# main.net
KiCad netlist of a schematic drawn in EAGLE
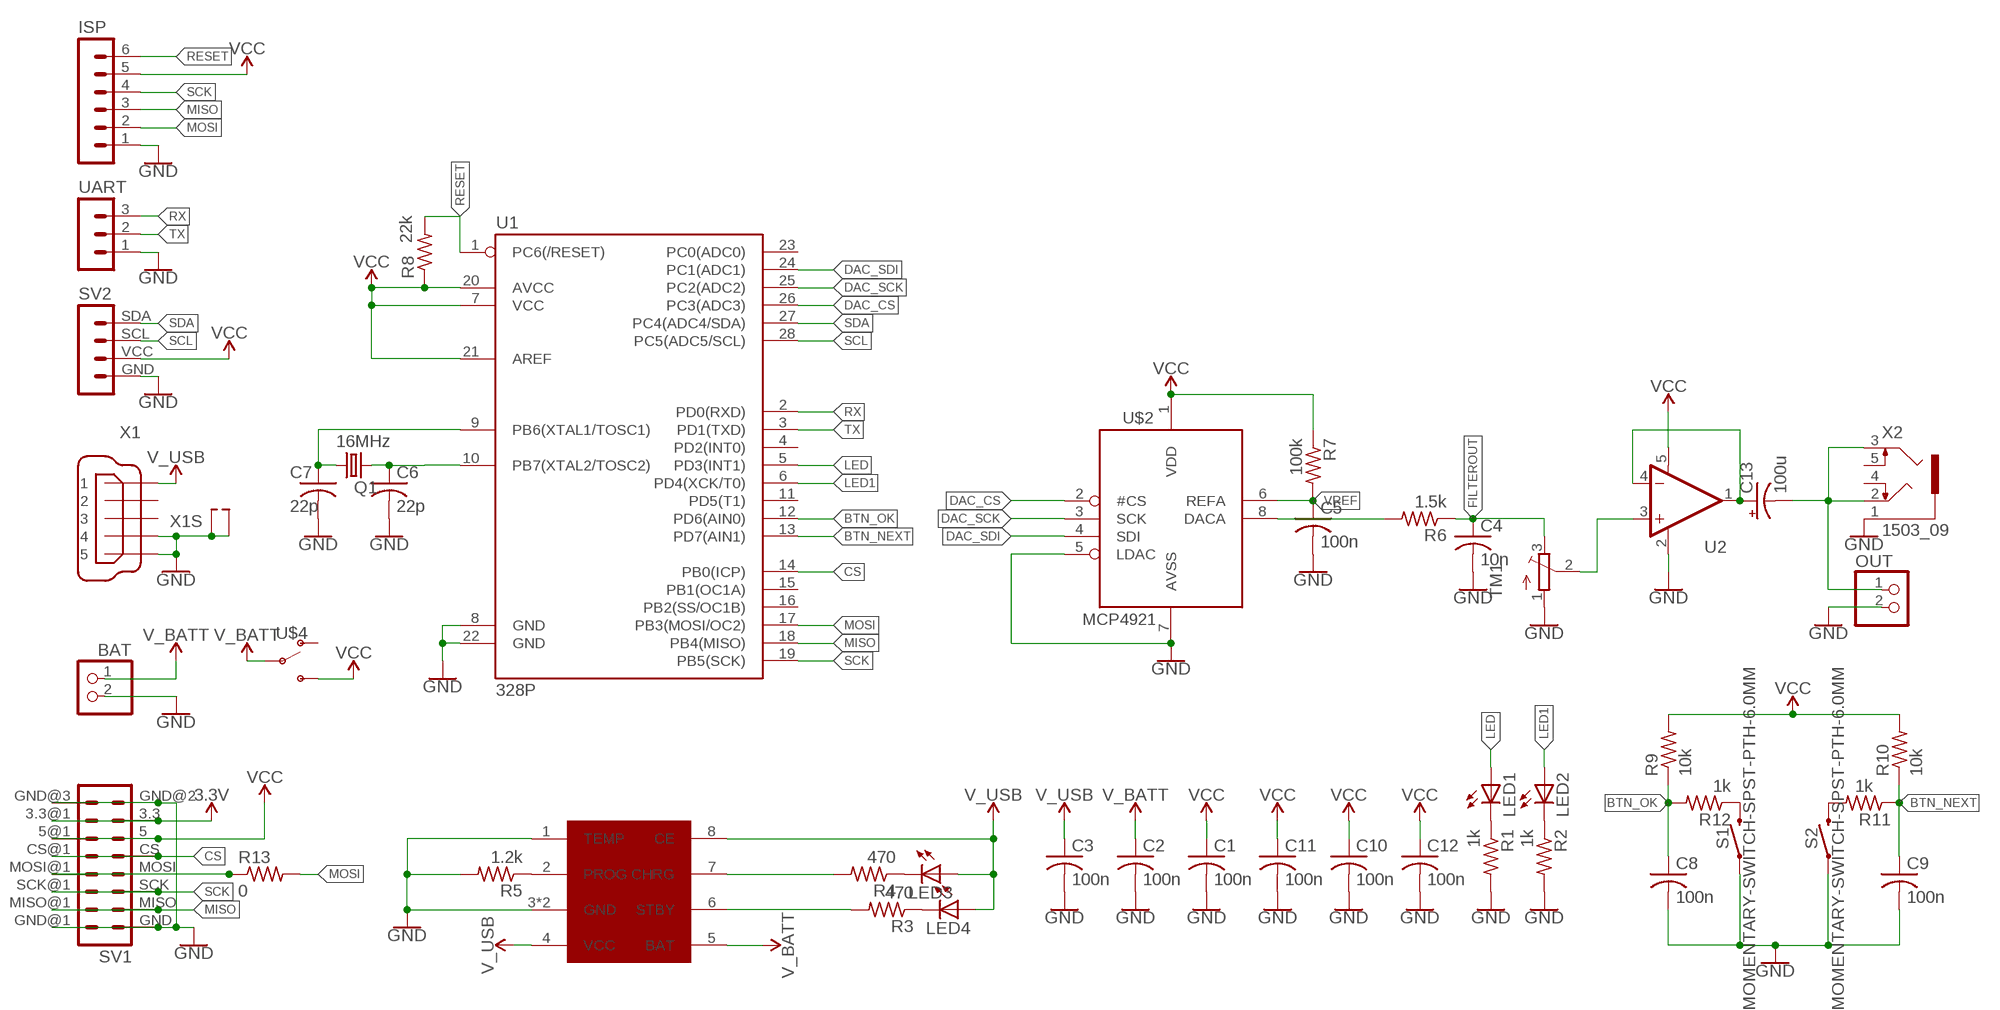
[diagram p0: schematic, sheet 1]

(export (version "E")
  (design (tool "Eeschema 10.0.6"))
  (components
    (comp (ref "BAT")
      (value "PINHD-1X2")
      (footprint "eagle-import:1X02")
      (libsource (lib "eagle-import") (part "PINHD-1X2"))
    )
    (comp (ref "C1")
      (value "100n")
      (footprint "eagle-import:C0603")
      (libsource (lib "eagle-import") (part "C-USC0603"))
    )
    (comp (ref "C2")
      (value "100n")
      (footprint "eagle-import:C0603")
      (libsource (lib "eagle-import") (part "C-USC0603"))
    )
    (comp (ref "C3")
      (value "100n")
      (footprint "eagle-import:C0603")
      (libsource (lib "eagle-import") (part "C-USC0603"))
    )
    (comp (ref "C4")
      (value "10n")
      (footprint "eagle-import:C0603")
      (libsource (lib "eagle-import") (part "C-USC0603"))
    )
    (comp (ref "C5")
      (value "100n")
      (footprint "eagle-import:C0603")
      (libsource (lib "eagle-import") (part "C-USC0603"))
    )
    (comp (ref "C6")
      (value "22p")
      (footprint "eagle-import:C0603")
      (libsource (lib "eagle-import") (part "C-USC0603"))
    )
    (comp (ref "C7")
      (value "22p")
      (footprint "eagle-import:C0603")
      (libsource (lib "eagle-import") (part "C-USC0603"))
    )
    (comp (ref "C8")
      (value "100n")
      (footprint "eagle-import:C0603")
      (libsource (lib "eagle-import") (part "C-USC0603"))
    )
    (comp (ref "C9")
      (value "100n")
      (footprint "eagle-import:C0603")
      (libsource (lib "eagle-import") (part "C-USC0603"))
    )
    (comp (ref "C10")
      (value "100n")
      (footprint "eagle-import:C0603")
      (libsource (lib "eagle-import") (part "C-USC0603"))
    )
    (comp (ref "C11")
      (value "100n")
      (footprint "eagle-import:C0603")
      (libsource (lib "eagle-import") (part "C-USC0603"))
    )
    (comp (ref "C12")
      (value "100n")
      (footprint "eagle-import:C0603")
      (libsource (lib "eagle-import") (part "C-USC0603"))
    )
    (comp (ref "C13")
      (value "100u")
      (footprint "eagle-import:E2,5-6E")
      (libsource (lib "eagle-import") (part "CPOL-USE2,5-6E"))
    )
    (comp (ref "CH1")
      (value "TP4056")
      (footprint "eagle-import:SOP8")
      (libsource (lib "eagle-import") (part "TP4056"))
    )
    (comp (ref "ISP")
      (value "MA06-1")
      (footprint "eagle-import:MA06-1")
      (libsource (lib "eagle-import") (part "MA06-1"))
    )
    (comp (ref "LED1")
      (value "LED3MM")
      (footprint "eagle-import:LED3MM")
      (libsource (lib "eagle-import") (part "LED3MM"))
    )
    (comp (ref "LED2")
      (value "LED3MM")
      (footprint "eagle-import:LED3MM")
      (libsource (lib "eagle-import") (part "LED3MM"))
    )
    (comp (ref "LED3")
      (value "LED3MM")
      (footprint "eagle-import:LED3MM")
      (libsource (lib "eagle-import") (part "LED3MM"))
    )
    (comp (ref "LED4")
      (value "LED3MM")
      (footprint "eagle-import:LED3MM")
      (libsource (lib "eagle-import") (part "LED3MM"))
    )
    (comp (ref "OUT")
      (value "PINHD-1X2")
      (footprint "eagle-import:1X02")
      (libsource (lib "eagle-import") (part "PINHD-1X2"))
    )
    (comp (ref "Q1")
      (value "16MHz")
      (footprint "eagle-import:HC49_S")
      (libsource (lib "eagle-import") (part "CRYSTALHC49S"))
    )
    (comp (ref "R1")
      (value "1k")
      (footprint "eagle-import:R0603")
      (libsource (lib "eagle-import") (part "R-US_R0603"))
    )
    (comp (ref "R2")
      (value "1k")
      (footprint "eagle-import:R0603")
      (libsource (lib "eagle-import") (part "R-US_R0603"))
    )
    (comp (ref "R3")
      (value "470")
      (footprint "eagle-import:R0603")
      (libsource (lib "eagle-import") (part "R-US_R0603"))
    )
    (comp (ref "R4")
      (value "470")
      (footprint "eagle-import:R0603")
      (libsource (lib "eagle-import") (part "R-US_R0603"))
    )
    (comp (ref "R5")
      (value "1.2k")
      (footprint "eagle-import:R0603")
      (libsource (lib "eagle-import") (part "R-US_R0603"))
    )
    (comp (ref "R6")
      (value "1.5k")
      (footprint "eagle-import:R0603")
      (libsource (lib "eagle-import") (part "R-US_R0603"))
    )
    (comp (ref "R7")
      (value "100k")
      (footprint "eagle-import:R0603")
      (libsource (lib "eagle-import") (part "R-US_R0603"))
    )
    (comp (ref "R8")
      (value "22k")
      (footprint "eagle-import:R0603")
      (libsource (lib "eagle-import") (part "R-US_R0603"))
    )
    (comp (ref "R9")
      (value "10k")
      (footprint "eagle-import:R0603")
      (libsource (lib "eagle-import") (part "R-US_R0603"))
    )
    (comp (ref "R10")
      (value "10k")
      (footprint "eagle-import:R0603")
      (libsource (lib "eagle-import") (part "R-US_R0603"))
    )
    (comp (ref "R11")
      (value "1k")
      (footprint "eagle-import:R0603")
      (libsource (lib "eagle-import") (part "R-US_R0603"))
    )
    (comp (ref "R12")
      (value "1k")
      (footprint "eagle-import:R0603")
      (libsource (lib "eagle-import") (part "R-US_R0603"))
    )
    (comp (ref "R13")
      (value "0")
      (footprint "eagle-import:0204_5")
      (libsource (lib "eagle-import") (part "R-US_0204/5"))
    )
    (comp (ref "S1")
      (value "MOMENTARY-SWITCH-SPST-PTH-6.0MM")
      (footprint "eagle-import:TACTILE_SWITCH_PTH_6.0MM")
      (libsource (lib "eagle-import") (part "MOMENTARY-SWITCH-SPST-PTH-6.0MM"))
    )
    (comp (ref "S2")
      (value "MOMENTARY-SWITCH-SPST-PTH-6.0MM")
      (footprint "eagle-import:TACTILE_SWITCH_PTH_6.0MM")
      (libsource (lib "eagle-import") (part "MOMENTARY-SWITCH-SPST-PTH-6.0MM"))
    )
    (comp (ref "SV1")
      (value "SD_CARD")
      (footprint "eagle-import:SD_CARD")
      (libsource (lib "eagle-import") (part "SD_CARD"))
    )
    (comp (ref "SV2")
      (value "OLED")
      (footprint "eagle-import:OLED")
      (libsource (lib "eagle-import") (part "OLED"))
    )
    (comp (ref "TM1")
      (value "TRIMPOT3386")
      (footprint "eagle-import:TRIM-3386")
      (libsource (lib "eagle-import") (part "TRIMPOT3386"))
    )
    (comp (ref "U$2")
      (value "MCP4921")
      (footprint "eagle-import:DIL08")
      (libsource (lib "eagle-import") (part "MCP4921"))
    )
    (comp (ref "U$4")
      (value "PC_SPDT_SWITCH")
      (footprint "eagle-import:PC_SPDT_SWITCH")
      (libsource (lib "eagle-import") (part "PC_SPDT_SWITCH"))
    )
    (comp (ref "U1")
      (value "328P")
      (footprint "eagle-import:DIP28")
      (libsource (lib "eagle-import") (part "ATMEGA328P_PDIP"))
    )
    (comp (ref "U2")
      (value "MCP6291T")
      (footprint "eagle-import:SOT23-5")
      (libsource (lib "eagle-import") (part "LMC7101T-E/OT"))
    )
    (comp (ref "UART")
      (value "MA03-1")
      (footprint "eagle-import:MA03-1")
      (libsource (lib "eagle-import") (part "MA03-1"))
    )
    (comp (ref "X1")
      (value "MINI-USB_SHIELD5P2-32005-601")
      (footprint "eagle-import:32005-601")
      (libsource (lib "eagle-import") (part "MINI-USB_SHIELD5P2-32005-601"))
    )
    (comp (ref "X2")
      (value "1503_09")
      (footprint "eagle-import:1503_09")
      (libsource (lib "eagle-import") (part "1503_09"))
    )
  )
  (nets
    (net (code "1") (name "3.3V") (class "Default")
      (node (ref "SV1") (pin "3.3") (pinfunction "3.3_3.3") (pintype "passive"))
      (node (ref "SV1") (pin "3.3@1") (pinfunction "3.3_3.3@1") (pintype "passive"))
    )
    (net (code "2") (name "BTN_NEXT") (class "Default")
      (node (ref "C9") (pin "1") (pinfunction "1_1") (pintype "passive"))
      (node (ref "R10") (pin "1") (pinfunction "1_1") (pintype "passive"))
      (node (ref "R11") (pin "1") (pinfunction "1_1") (pintype "passive"))
      (node (ref "U1") (pin "13") (pinfunction "PD7(AIN1)_13") (pintype "bidirectional"))
    )
    (net (code "3") (name "BTN_OK") (class "Default")
      (node (ref "C8") (pin "1") (pinfunction "1_1") (pintype "passive"))
      (node (ref "R12") (pin "2") (pinfunction "2_2") (pintype "passive"))
      (node (ref "R9") (pin "1") (pinfunction "1_1") (pintype "passive"))
      (node (ref "U1") (pin "12") (pinfunction "PD6(AIN0)_12") (pintype "bidirectional"))
    )
    (net (code "4") (name "CS") (class "Default")
      (node (ref "SV1") (pin "CS") (pinfunction "CS_CS") (pintype "passive"))
      (node (ref "SV1") (pin "CS@1") (pinfunction "CS_CS@1") (pintype "passive"))
      (node (ref "U1") (pin "14") (pinfunction "PB0(ICP)_14") (pintype "bidirectional"))
    )
    (net (code "5") (name "DAC_CS") (class "Default")
      (node (ref "U$2") (pin "2") (pinfunction "#CS_2") (pintype "input"))
      (node (ref "U1") (pin "26") (pinfunction "PC3(ADC3)_26") (pintype "bidirectional"))
    )
    (net (code "6") (name "DAC_SCK") (class "Default")
      (node (ref "U$2") (pin "3") (pinfunction "SCK_3") (pintype "input"))
      (node (ref "U1") (pin "25") (pinfunction "PC2(ADC2)_25") (pintype "bidirectional"))
    )
    (net (code "7") (name "DAC_SDI") (class "Default")
      (node (ref "U$2") (pin "4") (pinfunction "SDI_4") (pintype "input"))
      (node (ref "U1") (pin "24") (pinfunction "PC1(ADC1)_24") (pintype "bidirectional"))
    )
    (net (code "8") (name "FILTEROUT") (class "Default")
      (node (ref "C4") (pin "1") (pinfunction "1_1") (pintype "passive"))
      (node (ref "R6") (pin "1") (pinfunction "1_1") (pintype "passive"))
      (node (ref "TM1") (pin "3") (pinfunction "E_3") (pintype "passive"))
    )
    (net (code "9") (name "GND") (class "Default")
      (node (ref "BAT") (pin "2") (pinfunction "2_2") (pintype "passive"))
      (node (ref "C1") (pin "2") (pinfunction "2_2") (pintype "passive"))
      (node (ref "C10") (pin "2") (pinfunction "2_2") (pintype "passive"))
      (node (ref "C11") (pin "2") (pinfunction "2_2") (pintype "passive"))
      (node (ref "C12") (pin "2") (pinfunction "2_2") (pintype "passive"))
      (node (ref "C2") (pin "2") (pinfunction "2_2") (pintype "passive"))
      (node (ref "C3") (pin "2") (pinfunction "2_2") (pintype "passive"))
      (node (ref "C4") (pin "2") (pinfunction "2_2") (pintype "passive"))
      (node (ref "C5") (pin "2") (pinfunction "2_2") (pintype "passive"))
      (node (ref "C6") (pin "2") (pinfunction "2_2") (pintype "passive"))
      (node (ref "C7") (pin "2") (pinfunction "2_2") (pintype "passive"))
      (node (ref "C8") (pin "2") (pinfunction "2_2") (pintype "passive"))
      (node (ref "C9") (pin "2") (pinfunction "2_2") (pintype "passive"))
      (node (ref "CH1") (pin "1") (pinfunction "TEMP_1") (pintype "bidirectional"))
      (node (ref "CH1") (pin "3") (pinfunction "GND_3") (pintype "bidirectional"))
      (node (ref "CH1") (pin "9") (pinfunction "GND_9") (pintype "bidirectional"))
      (node (ref "ISP") (pin "1") (pinfunction "1_1") (pintype "passive"))
      (node (ref "OUT") (pin "2") (pinfunction "2_2") (pintype "passive"))
      (node (ref "R1") (pin "2") (pinfunction "2_2") (pintype "passive"))
      (node (ref "R2") (pin "2") (pinfunction "2_2") (pintype "passive"))
      (node (ref "R5") (pin "2") (pinfunction "2_2") (pintype "passive"))
      (node (ref "S1") (pin "1") (pinfunction "1_1") (pintype "passive"))
      (node (ref "S2") (pin "1") (pinfunction "1_1") (pintype "passive"))
      (node (ref "SV1") (pin "GND") (pinfunction "GND_GND") (pintype "passive"))
      (node (ref "SV1") (pin "GND@1") (pinfunction "GND_GND@1") (pintype "passive"))
      (node (ref "SV1") (pin "GND@2") (pinfunction "GND_GND@2") (pintype "passive"))
      (node (ref "SV1") (pin "GND@3") (pinfunction "GND_GND@3") (pintype "passive"))
      (node (ref "SV2") (pin "GND") (pinfunction "GND_GND") (pintype "passive"))
      (node (ref "TM1") (pin "1") (pinfunction "A_1") (pintype "passive"))
      (node (ref "U$2") (pin "5") (pinfunction "LDAC_5") (pintype "input"))
      (node (ref "U$2") (pin "7") (pinfunction "AVSS_7") (pintype "power_in"))
      (node (ref "U1") (pin "22") (pinfunction "GND_22") (pintype "bidirectional"))
      (node (ref "U1") (pin "8") (pinfunction "GND_8") (pintype "bidirectional"))
      (node (ref "U2") (pin "2") (pinfunction "V-_2") (pintype "power_in"))
      (node (ref "UART") (pin "1") (pinfunction "1_1") (pintype "passive"))
      (node (ref "X1") (pin "4") (pinfunction "4_4") (pintype "passive"))
      (node (ref "X1") (pin "5") (pinfunction "5_5") (pintype "passive"))
      (node (ref "X1") (pin "M1") (pinfunction "S1_M1") (pintype "passive"))
      (node (ref "X1") (pin "M2") (pinfunction "S2_M2") (pintype "passive"))
      (node (ref "X2") (pin "1") (pinfunction "1_1") (pintype "passive"))
    )
    (net (code "10") (name "LED") (class "Default")
      (node (ref "LED1") (pin "A") (pinfunction "A_A") (pintype "passive"))
      (node (ref "U1") (pin "5") (pinfunction "PD3(INT1)_5") (pintype "bidirectional"))
    )
    (net (code "11") (name "LED1") (class "Default")
      (node (ref "LED2") (pin "A") (pinfunction "A_A") (pintype "passive"))
      (node (ref "U1") (pin "6") (pinfunction "PD4(XCK/T0)_6") (pintype "bidirectional"))
    )
    (net (code "12") (name "MISO") (class "Default")
      (node (ref "ISP") (pin "3") (pinfunction "3_3") (pintype "passive"))
      (node (ref "SV1") (pin "MISO") (pinfunction "MISO_MISO") (pintype "passive"))
      (node (ref "SV1") (pin "MISO@1") (pinfunction "MISO_MISO@1") (pintype "passive"))
      (node (ref "U1") (pin "18") (pinfunction "PB4(MISO)_18") (pintype "bidirectional"))
    )
    (net (code "13") (name "MOSI") (class "Default")
      (node (ref "ISP") (pin "2") (pinfunction "2_2") (pintype "passive"))
      (node (ref "R13") (pin "2") (pinfunction "2_2") (pintype "passive"))
      (node (ref "U1") (pin "17") (pinfunction "PB3(MOSI/OC2)_17") (pintype "bidirectional"))
    )
    (net (code "14") (name "Net-(C13-Pad-)") (class "Default")
      (node (ref "C13") (pin "-") (pinfunction "-_-") (pintype "passive"))
      (node (ref "OUT") (pin "1") (pinfunction "1_1") (pintype "passive"))
      (node (ref "X2") (pin "2") (pinfunction "2_2") (pintype "passive"))
      (node (ref "X2") (pin "3") (pinfunction "3_3") (pintype "passive"))
    )
    (net (code "15") (name "Net-(CH1-CHRG)") (class "Default")
      (node (ref "CH1") (pin "7") (pinfunction "CHRG_7") (pintype "bidirectional"))
      (node (ref "R4") (pin "2") (pinfunction "2_2") (pintype "passive"))
    )
    (net (code "16") (name "Net-(CH1-PROG)") (class "Default")
      (node (ref "CH1") (pin "2") (pinfunction "PROG_2") (pintype "bidirectional"))
      (node (ref "R5") (pin "1") (pinfunction "1_1") (pintype "passive"))
    )
    (net (code "17") (name "Net-(CH1-STBY)") (class "Default")
      (node (ref "CH1") (pin "6") (pinfunction "STBY_6") (pintype "bidirectional"))
      (node (ref "R3") (pin "2") (pinfunction "2_2") (pintype "passive"))
    )
    (net (code "18") (name "Net-(LED1-C)") (class "Default")
      (node (ref "LED1") (pin "K") (pinfunction "C_K") (pintype "passive"))
      (node (ref "R1") (pin "1") (pinfunction "1_1") (pintype "passive"))
    )
    (net (code "19") (name "Net-(LED2-C)") (class "Default")
      (node (ref "LED2") (pin "K") (pinfunction "C_K") (pintype "passive"))
      (node (ref "R2") (pin "1") (pinfunction "1_1") (pintype "passive"))
    )
    (net (code "20") (name "Net-(LED3-C)") (class "Default")
      (node (ref "LED3") (pin "K") (pinfunction "C_K") (pintype "passive"))
      (node (ref "R4") (pin "1") (pinfunction "1_1") (pintype "passive"))
    )
    (net (code "21") (name "Net-(LED4-C)") (class "Default")
      (node (ref "LED4") (pin "K") (pinfunction "C_K") (pintype "passive"))
      (node (ref "R3") (pin "1") (pinfunction "1_1") (pintype "passive"))
    )
    (net (code "22") (name "Net-(R13-Pad1)") (class "Default")
      (node (ref "R13") (pin "1") (pinfunction "1_1") (pintype "passive"))
      (node (ref "SV1") (pin "MOSI") (pinfunction "MOSI_MOSI") (pintype "passive"))
      (node (ref "SV1") (pin "MOSI@1") (pinfunction "MOSI_MOSI@1") (pintype "passive"))
    )
    (net (code "23") (name "Net-(S1-2)") (class "Default")
      (node (ref "R12") (pin "1") (pinfunction "1_1") (pintype "passive"))
      (node (ref "S1") (pin "3") (pinfunction "2_3") (pintype "passive"))
    )
    (net (code "24") (name "Net-(S2-2)") (class "Default")
      (node (ref "R11") (pin "2") (pinfunction "2_2") (pintype "passive"))
      (node (ref "S2") (pin "3") (pinfunction "2_3") (pintype "passive"))
    )
    (net (code "25") (name "Net-(TM1-S)") (class "Default")
      (node (ref "TM1") (pin "2") (pinfunction "S_2") (pintype "passive"))
      (node (ref "U2") (pin "3") (pinfunction "+IN_3") (pintype "input"))
    )
    (net (code "26") (name "Net-(U$2-DACA)") (class "Default")
      (node (ref "R6") (pin "2") (pinfunction "2_2") (pintype "passive"))
      (node (ref "U$2") (pin "8") (pinfunction "DACA_8") (pintype "output"))
    )
    (net (code "27") (name "Net-(U1-PB6(XTAL1{slash}TOSC1))") (class "Default")
      (node (ref "C7") (pin "1") (pinfunction "1_1") (pintype "passive"))
      (node (ref "Q1") (pin "1") (pinfunction "1_1") (pintype "passive"))
      (node (ref "U1") (pin "9") (pinfunction "PB6(XTAL1/TOSC1)_9") (pintype "bidirectional"))
    )
    (net (code "28") (name "Net-(U1-PB7(XTAL2{slash}TOSC2))") (class "Default")
      (node (ref "C6") (pin "1") (pinfunction "1_1") (pintype "passive"))
      (node (ref "Q1") (pin "2") (pinfunction "2_2") (pintype "passive"))
      (node (ref "U1") (pin "10") (pinfunction "PB7(XTAL2/TOSC2)_10") (pintype "bidirectional"))
    )
    (net (code "29") (name "Net-(U2--IN)") (class "Default")
      (node (ref "C13") (pin "+") (pinfunction "+_+") (pintype "passive"))
      (node (ref "U2") (pin "1") (pinfunction "OUT_1") (pintype "output"))
      (node (ref "U2") (pin "4") (pinfunction "-IN_4") (pintype "input"))
    )
    (net (code "30") (name "RESET") (class "Default")
      (node (ref "ISP") (pin "6") (pinfunction "6_6") (pintype "passive"))
      (node (ref "R8") (pin "2") (pinfunction "2_2") (pintype "passive"))
      (node (ref "U1") (pin "1") (pinfunction "PC6(/RESET)_1") (pintype "bidirectional"))
    )
    (net (code "31") (name "RX") (class "Default")
      (node (ref "U1") (pin "2") (pinfunction "PD0(RXD)_2") (pintype "bidirectional"))
      (node (ref "UART") (pin "3") (pinfunction "3_3") (pintype "passive"))
    )
    (net (code "32") (name "SCK") (class "Default")
      (node (ref "ISP") (pin "4") (pinfunction "4_4") (pintype "passive"))
      (node (ref "SV1") (pin "SCK") (pinfunction "SCK_SCK") (pintype "passive"))
      (node (ref "SV1") (pin "SCK@1") (pinfunction "SCK_SCK@1") (pintype "passive"))
      (node (ref "U1") (pin "19") (pinfunction "PB5(SCK)_19") (pintype "bidirectional"))
    )
    (net (code "33") (name "SCL") (class "Default")
      (node (ref "SV2") (pin "SCL") (pinfunction "SCL_SCL") (pintype "passive"))
      (node (ref "U1") (pin "28") (pinfunction "PC5(ADC5/SCL)_28") (pintype "bidirectional"))
    )
    (net (code "34") (name "SDA") (class "Default")
      (node (ref "SV2") (pin "SDA") (pinfunction "SDA_SDA") (pintype "passive"))
      (node (ref "U1") (pin "27") (pinfunction "PC4(ADC4/SDA)_27") (pintype "bidirectional"))
    )
    (net (code "35") (name "TX") (class "Default")
      (node (ref "U1") (pin "3") (pinfunction "PD1(TXD)_3") (pintype "bidirectional"))
      (node (ref "UART") (pin "2") (pinfunction "2_2") (pintype "passive"))
    )
    (net (code "36") (name "VCC") (class "Default")
      (node (ref "C1") (pin "1") (pinfunction "1_1") (pintype "passive"))
      (node (ref "C10") (pin "1") (pinfunction "1_1") (pintype "passive"))
      (node (ref "C11") (pin "1") (pinfunction "1_1") (pintype "passive"))
      (node (ref "C12") (pin "1") (pinfunction "1_1") (pintype "passive"))
      (node (ref "ISP") (pin "5") (pinfunction "5_5") (pintype "passive"))
      (node (ref "R10") (pin "2") (pinfunction "2_2") (pintype "passive"))
      (node (ref "R7") (pin "1") (pinfunction "1_1") (pintype "passive"))
      (node (ref "R8") (pin "1") (pinfunction "1_1") (pintype "passive"))
      (node (ref "R9") (pin "2") (pinfunction "2_2") (pintype "passive"))
      (node (ref "SV1") (pin "5") (pinfunction "5_5") (pintype "passive"))
      (node (ref "SV1") (pin "5@1") (pinfunction "5_5@1") (pintype "passive"))
      (node (ref "SV2") (pin "VCC") (pinfunction "VCC_VCC") (pintype "passive"))
      (node (ref "U$2") (pin "1") (pinfunction "VDD_1") (pintype "power_in"))
      (node (ref "U$4") (pin "NO") (pinfunction "NO_NO") (pintype "passive"))
      (node (ref "U1") (pin "20") (pinfunction "AVCC_20") (pintype "bidirectional"))
      (node (ref "U1") (pin "21") (pinfunction "AREF_21") (pintype "bidirectional"))
      (node (ref "U1") (pin "7") (pinfunction "VCC_7") (pintype "bidirectional"))
      (node (ref "U2") (pin "5") (pinfunction "V+_5") (pintype "power_in"))
    )
    (net (code "37") (name "VREF") (class "Default")
      (node (ref "C5") (pin "1") (pinfunction "1_1") (pintype "passive"))
      (node (ref "R7") (pin "2") (pinfunction "2_2") (pintype "passive"))
      (node (ref "U$2") (pin "6") (pinfunction "REFA_6") (pintype "input"))
    )
    (net (code "38") (name "V_BATT") (class "Default")
      (node (ref "BAT") (pin "1") (pinfunction "1_1") (pintype "passive"))
      (node (ref "C2") (pin "1") (pinfunction "1_1") (pintype "passive"))
      (node (ref "CH1") (pin "5") (pinfunction "BAT_5") (pintype "bidirectional"))
      (node (ref "U$4") (pin "COM") (pinfunction "COM_COM") (pintype "passive"))
    )
    (net (code "39") (name "V_USB") (class "Default")
      (node (ref "C3") (pin "1") (pinfunction "1_1") (pintype "passive"))
      (node (ref "CH1") (pin "4") (pinfunction "VCC_4") (pintype "bidirectional"))
      (node (ref "CH1") (pin "8") (pinfunction "CE_8") (pintype "bidirectional"))
      (node (ref "LED3") (pin "A") (pinfunction "A_A") (pintype "passive"))
      (node (ref "LED4") (pin "A") (pinfunction "A_A") (pintype "passive"))
      (node (ref "X1") (pin "1") (pinfunction "1_1") (pintype "passive"))
    )
    (net (code "40") (name "unconnected-(U$4-PadNC)") (class "Default")
      (node (ref "U$4") (pin "NC") (pinfunction "NC_NC") (pintype "passive"))
    )
    (net (code "41") (name "unconnected-(U1-PB1(OC1A)-Pad15)") (class "Default")
      (node (ref "U1") (pin "15") (pinfunction "PB1(OC1A)_15") (pintype "bidirectional"))
    )
    (net (code "42") (name "unconnected-(U1-PB2(SS{slash}OC1B)-Pad16)") (class "Default")
      (node (ref "U1") (pin "16") (pinfunction "PB2(SS/OC1B)_16") (pintype "bidirectional"))
    )
    (net (code "43") (name "unconnected-(U1-PC0(ADC0)-Pad23)") (class "Default")
      (node (ref "U1") (pin "23") (pinfunction "PC0(ADC0)_23") (pintype "bidirectional"))
    )
    (net (code "44") (name "unconnected-(U1-PD2(INT0)-Pad4)") (class "Default")
      (node (ref "U1") (pin "4") (pinfunction "PD2(INT0)_4") (pintype "bidirectional"))
    )
    (net (code "45") (name "unconnected-(U1-PD5(T1)-Pad11)") (class "Default")
      (node (ref "U1") (pin "11") (pinfunction "PD5(T1)_11") (pintype "bidirectional"))
    )
    (net (code "46") (name "unconnected-(X1-Pad2)") (class "Default")
      (node (ref "X1") (pin "2") (pinfunction "2_2") (pintype "passive"))
    )
    (net (code "47") (name "unconnected-(X1-Pad3)") (class "Default")
      (node (ref "X1") (pin "3") (pinfunction "3_3") (pintype "passive"))
    )
    (net (code "48") (name "unconnected-(X2-Pad4)") (class "Default")
      (node (ref "X2") (pin "4") (pinfunction "4_4") (pintype "passive"))
    )
    (net (code "49") (name "unconnected-(X2-Pad5)") (class "Default")
      (node (ref "X2") (pin "5") (pinfunction "5_5") (pintype "passive"))
    )
  )
)
